# ESP8266-Thing-Dev-4H.net
KiCad netlist of a schematic drawn in EAGLE
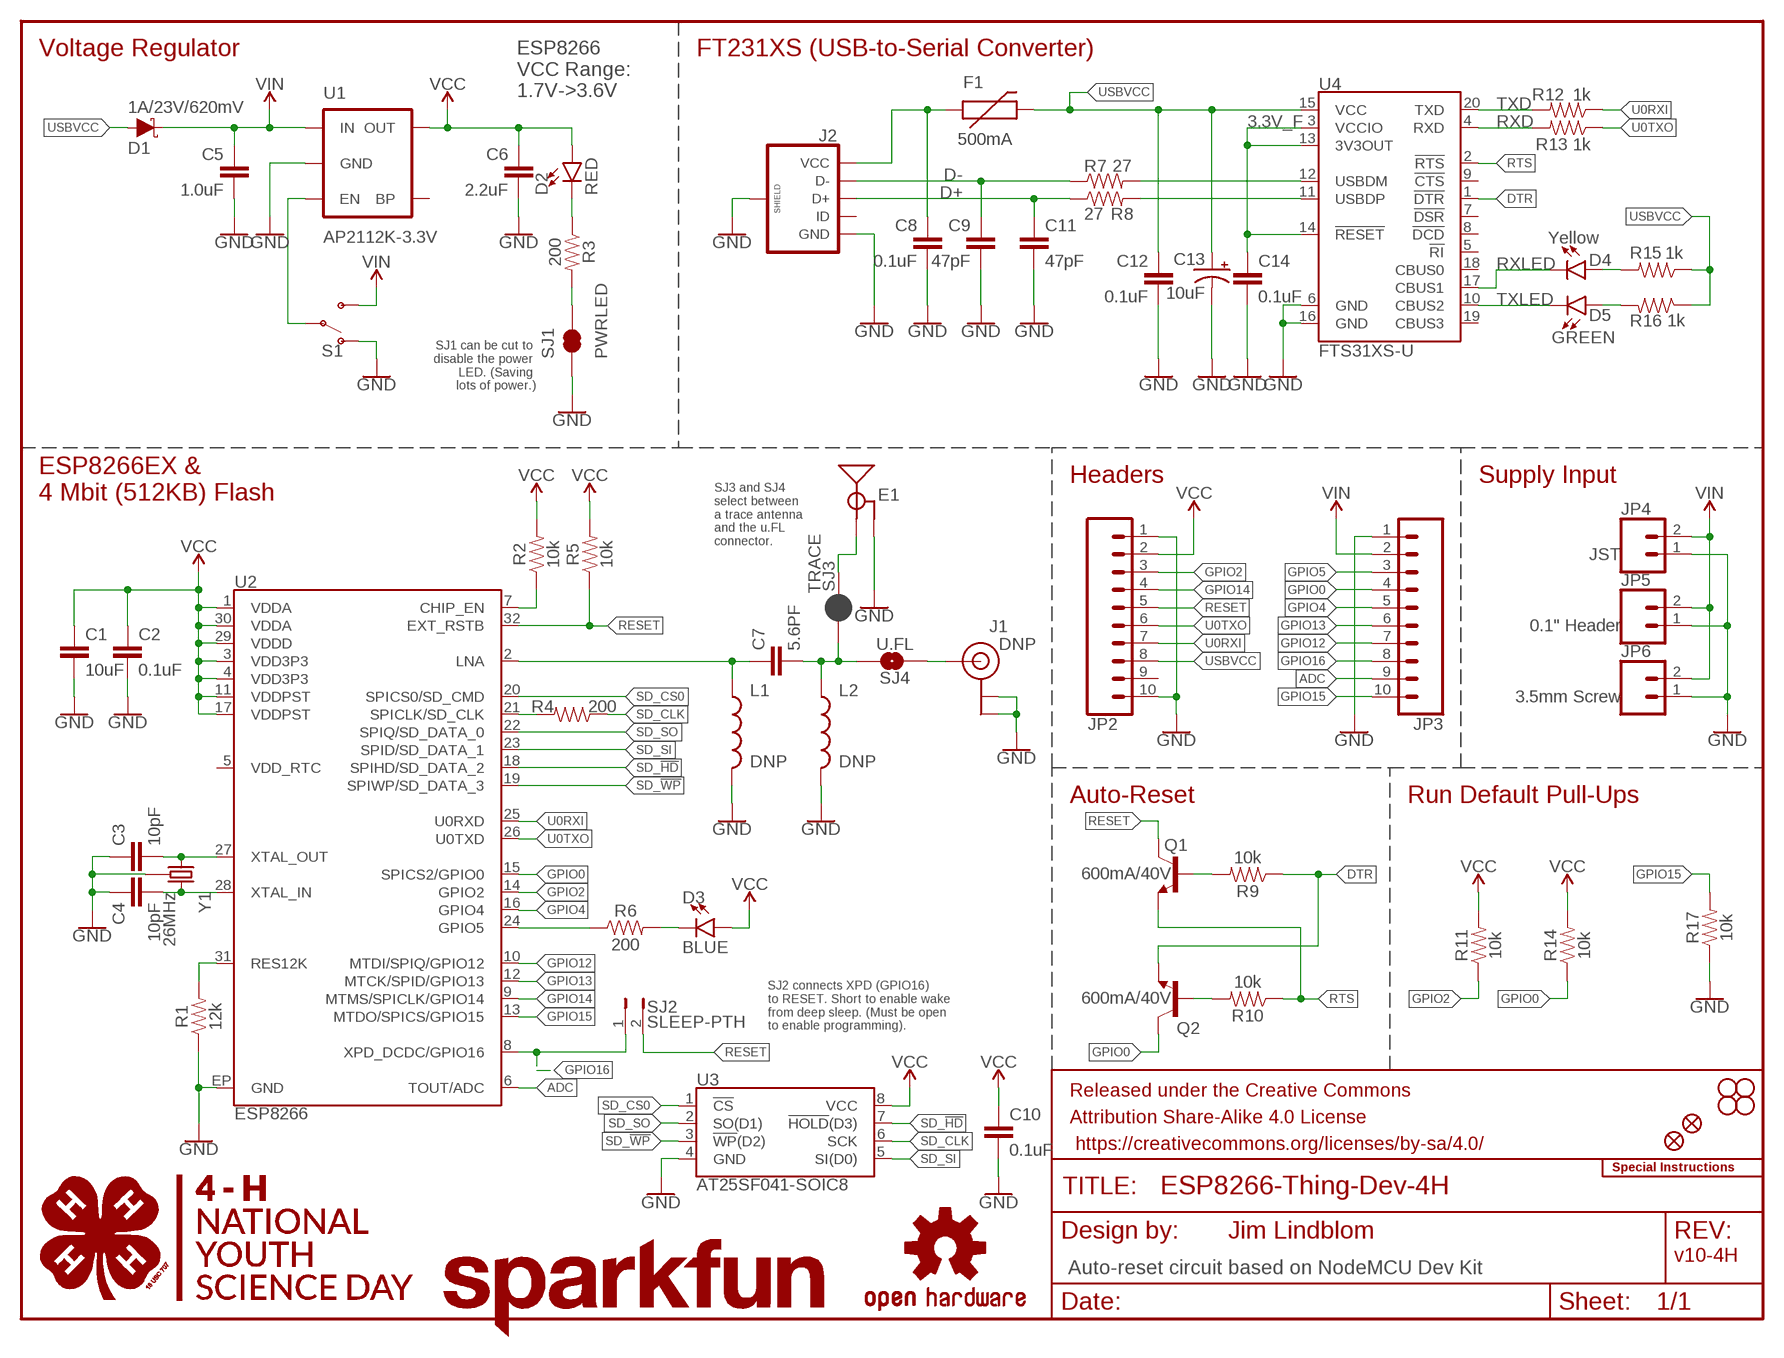
[diagram p0: schematic, sheet 1]

(export (version "E")
  (design (tool "Eeschema 10.0.6"))
  (components
    (comp (ref "C1")
      (value "10uF")
      (footprint "eagle-import:0603")
      (libsource (lib "eagle-import") (part "10UF-0603-6.3V-20%"))
    )
    (comp (ref "C2")
      (value "0.1uF")
      (footprint "eagle-import:0603")
      (libsource (lib "eagle-import") (part "0.1UF-0603-25V-(+80/-20%)"))
    )
    (comp (ref "C3")
      (value "10pF")
      (footprint "eagle-import:0603")
      (libsource (lib "eagle-import") (part "10PF-0603-50V-5%"))
    )
    (comp (ref "C4")
      (value "10pF")
      (footprint "eagle-import:0603")
      (libsource (lib "eagle-import") (part "10PF-0603-50V-5%"))
    )
    (comp (ref "C5")
      (value "1.0uF")
      (footprint "eagle-import:0805")
      (libsource (lib "eagle-import") (part "1.0UF-0805-25V-(+80/-20%)"))
    )
    (comp (ref "C6")
      (value "2.2uF")
      (footprint "eagle-import:0603")
      (libsource (lib "eagle-import") (part "2.2UF-0603-10V-20%"))
    )
    (comp (ref "C7")
      (value "5.6PF")
      (footprint "eagle-import:0603")
      (fields (field (name "PROD_ID") "CAP-12456"))
      (libsource (lib "eagle-import") (part "5.6PF-0603-50V-5%"))
    )
    (comp (ref "C8")
      (value "0.1uF")
      (footprint "eagle-import:0603")
      (libsource (lib "eagle-import") (part "0.1UF-0603-25V-(+80/-20%)"))
    )
    (comp (ref "C9")
      (value "47pF")
      (footprint "eagle-import:0603")
      (libsource (lib "eagle-import") (part "47PF-0603-50V-5%"))
    )
    (comp (ref "C10")
      (value "0.1uF")
      (footprint "eagle-import:0603")
      (libsource (lib "eagle-import") (part "0.1UF-0603-25V-(+80/-20%)"))
    )
    (comp (ref "C11")
      (value "47pF")
      (footprint "eagle-import:0603")
      (libsource (lib "eagle-import") (part "47PF-0603-50V-5%"))
    )
    (comp (ref "C12")
      (value "0.1uF")
      (footprint "eagle-import:0603")
      (libsource (lib "eagle-import") (part "0.1UF-0603-25V-(+80/-20%)"))
    )
    (comp (ref "C13")
      (value "10uF")
      (footprint "eagle-import:EIA3216")
      (libsource (lib "eagle-import") (part "10UF-POLAR-EIA3216-16V-10%(TANT)"))
    )
    (comp (ref "C14")
      (value "0.1uF")
      (footprint "eagle-import:0603")
      (libsource (lib "eagle-import") (part "0.1UF-0603-25V-(+80/-20%)"))
    )
    (comp (ref "D1")
      (value "1A/23V/620mV")
      (footprint "eagle-import:SOD-323")
      (libsource (lib "eagle-import") (part "DIODE-SCHOTTKY-BAT20J"))
    )
    (comp (ref "D2")
      (value "RED")
      (footprint "eagle-import:LED-0603")
      (libsource (lib "eagle-import") (part "LED-RED0603"))
    )
    (comp (ref "D3")
      (value "BLUE")
      (footprint "eagle-import:LED-0603")
      (libsource (lib "eagle-import") (part "LED-BLUE0603"))
    )
    (comp (ref "D4")
      (value "Yellow")
      (footprint "eagle-import:LED-0603")
      (libsource (lib "eagle-import") (part "LED-YELLOW0603"))
    )
    (comp (ref "D5")
      (value "GREEN")
      (footprint "eagle-import:LED-0603")
      (libsource (lib "eagle-import") (part "LED-GREEN0603"))
    )
    (comp (ref "E1")
      (value "ANTENNA-GROUNDEDTRACE-25.7MM")
      (footprint "eagle-import:TRACE_ANTENNA_2.4GHZ_25.7MM")
      (libsource (lib "eagle-import") (part "ANTENNA-GROUNDEDTRACE-25.7MM"))
    )
    (comp (ref "F1")
      (value "500mA")
      (footprint "eagle-import:PTC-1206")
      (libsource (lib "eagle-import") (part "PTCSMD"))
    )
    (comp (ref "FID1")
      (value "FIDUCIAL1X2")
      (footprint "eagle-import:FIDUCIAL-1X2")
      (libsource (lib "eagle-import") (part "FIDUCIAL1X2"))
    )
    (comp (ref "FID2")
      (value "FIDUCIAL1X2")
      (footprint "eagle-import:FIDUCIAL-1X2")
      (libsource (lib "eagle-import") (part "FIDUCIAL1X2"))
    )
    (comp (ref "FRAME1")
      (value "FRAME-LETTER")
      (footprint "eagle-import:CREATIVE_COMMONS")
      (libsource (lib "eagle-import") (part "FRAME-LETTER"))
    )
    (comp (ref "J1")
      (value "U.FL")
      (footprint "eagle-import:U.FL")
      (libsource (lib "eagle-import") (part "U.FL"))
    )
    (comp (ref "J2")
      (value "USB_MICROB_PLUGCONN-11752")
      (footprint "eagle-import:USB-B-MICRO-SMD_V03")
      (libsource (lib "eagle-import") (part "USB_MICROB_PLUGCONN-11752"))
    )
    (comp (ref "JP2")
      (value "CONN_10LOCK_NS")
      (footprint "eagle-import:1X10_LOCK_NS")
      (libsource (lib "eagle-import") (part "CONN_10LOCK_NS"))
    )
    (comp (ref "JP3")
      (value "CONN_10LOCK_NS")
      (footprint "eagle-import:1X10_LOCK_NS")
      (libsource (lib "eagle-import") (part "CONN_10LOCK_NS"))
    )
    (comp (ref "JP4")
      (value "CONN_02JST-PTH-2")
      (footprint "eagle-import:JST-2-PTH")
      (libsource (lib "eagle-import") (part "CONN_02JST-PTH-2"))
    )
    (comp (ref "JP5")
      (value "CONN_021X02_NO_SILK")
      (footprint "eagle-import:1X02_NO_SILK")
      (libsource (lib "eagle-import") (part "CONN_021X02_NO_SILK"))
    )
    (comp (ref "JP6")
      (value "CONN_023.5MM-NO_SILK")
      (footprint "eagle-import:SCREWTERMINAL-3.5MM-2-NS")
      (libsource (lib "eagle-import") (part "CONN_023.5MM-NO_SILK"))
    )
    (comp (ref "L1")
      (value "DNP")
      (footprint "eagle-import:0603")
      (libsource (lib "eagle-import") (part "INDUCTOR0603"))
    )
    (comp (ref "L2")
      (value "DNP")
      (footprint "eagle-import:0603")
      (libsource (lib "eagle-import") (part "INDUCTOR0603"))
    )
    (comp (ref "LOGO1")
      (value "SFE_LOGO_NAME.2_INCH")
      (footprint "eagle-import:SFE_LOGO_NAME_.2")
      (libsource (lib "eagle-import") (part "SFE_LOGO_NAME.2_INCH"))
    )
    (comp (ref "LOGO2")
      (value "OSHW-LOGOS")
      (footprint "eagle-import:OSHW-LOGO-S")
      (libsource (lib "eagle-import") (part "OSHW-LOGOS"))
    )
    (comp (ref "Q1")
      (value "600mA/40V")
      (footprint "eagle-import:SOT23-3")
      (libsource (lib "eagle-import") (part "TRANS_NPN-MMBT2222AL"))
    )
    (comp (ref "Q2")
      (value "600mA/40V")
      (footprint "eagle-import:SOT23-3")
      (libsource (lib "eagle-import") (part "TRANS_NPN-MMBT2222AL"))
    )
    (comp (ref "R1")
      (value "12k")
      (footprint "eagle-import:0603")
      (libsource (lib "eagle-import") (part "12KOHM-0603-1/10W-1%"))
    )
    (comp (ref "R2")
      (value "10k")
      (footprint "eagle-import:0603")
      (libsource (lib "eagle-import") (part "10KOHM-0603-1/10W-1%"))
    )
    (comp (ref "R3")
      (value "200")
      (footprint "eagle-import:0603")
      (libsource (lib "eagle-import") (part "200OHM-0603-1/10W-1%"))
    )
    (comp (ref "R4")
      (value "200")
      (footprint "eagle-import:0603")
      (libsource (lib "eagle-import") (part "200OHM-0603-1/10W-1%"))
    )
    (comp (ref "R5")
      (value "10k")
      (footprint "eagle-import:0603")
      (libsource (lib "eagle-import") (part "10KOHM-0603-1/10W-1%"))
    )
    (comp (ref "R6")
      (value "200")
      (footprint "eagle-import:0603")
      (libsource (lib "eagle-import") (part "200OHM-0603-1/10W-1%"))
    )
    (comp (ref "R7")
      (value "27")
      (footprint "eagle-import:0603")
      (libsource (lib "eagle-import") (part "27OHM-0603-1/10W-1%"))
    )
    (comp (ref "R8")
      (value "27")
      (footprint "eagle-import:0603")
      (libsource (lib "eagle-import") (part "27OHM-0603-1/10W-1%"))
    )
    (comp (ref "R9")
      (value "10k")
      (footprint "eagle-import:0603")
      (libsource (lib "eagle-import") (part "10KOHM-0603-1/10W-1%"))
    )
    (comp (ref "R10")
      (value "10k")
      (footprint "eagle-import:0603")
      (libsource (lib "eagle-import") (part "10KOHM-0603-1/10W-1%"))
    )
    (comp (ref "R11")
      (value "10k")
      (footprint "eagle-import:0603")
      (libsource (lib "eagle-import") (part "10KOHM-0603-1/10W-1%"))
    )
    (comp (ref "R12")
      (value "1k")
      (footprint "eagle-import:0603")
      (libsource (lib "eagle-import") (part "1KOHM-0603-1/10W-1%"))
    )
    (comp (ref "R13")
      (value "1k")
      (footprint "eagle-import:0603")
      (libsource (lib "eagle-import") (part "1KOHM-0603-1/10W-1%"))
    )
    (comp (ref "R14")
      (value "10k")
      (footprint "eagle-import:0603")
      (libsource (lib "eagle-import") (part "10KOHM-0603-1/10W-1%"))
    )
    (comp (ref "R15")
      (value "1k")
      (footprint "eagle-import:0603")
      (libsource (lib "eagle-import") (part "1KOHM-0603-1/10W-1%"))
    )
    (comp (ref "R16")
      (value "1k")
      (footprint "eagle-import:0603")
      (libsource (lib "eagle-import") (part "1KOHM-0603-1/10W-1%"))
    )
    (comp (ref "R17")
      (value "10k")
      (footprint "eagle-import:0603")
      (libsource (lib "eagle-import") (part "10KOHM-0603-1/10W-1%"))
    )
    (comp (ref "S1")
      (value "SWITCH-SPDT-SMD-RIGHT-ANGLE")
      (footprint "eagle-import:SWITCH_SPST_SMD_A")
      (fields (field (name "PROD_ID") "SWCH-10651"))
      (libsource (lib "eagle-import") (part "SWITCH-SPDT-SMD-RIGHT-ANGLE"))
    )
    (comp (ref "SJ1")
      (value "PWRLED")
      (footprint "eagle-import:PAD-JUMPER-2-NC_BY_TRACE_YES_SILK")
      (libsource (lib "eagle-import") (part "JUMPER-PAD-2-NC_BY_TRACE"))
    )
    (comp (ref "SJ2")
      (value "SLEEP-PTH")
      (footprint "eagle-import:PTH-JUMPER-2-NO_NO_SILK")
      (libsource (lib "eagle-import") (part "JUMPER-PTH-2-NO"))
    )
    (comp (ref "SJ3")
      (value "TRACE")
      (footprint "eagle-import:PAD-JUMPER-2-NC_BY_PASTE_NO_SILK")
      (libsource (lib "eagle-import") (part "JUMPER-PAD-2-NC_BY_PASTENO-SILK"))
    )
    (comp (ref "SJ4")
      (value "U.FL")
      (footprint "eagle-import:PAD-JUMPER-2-NO_NO_SILK")
      (libsource (lib "eagle-import") (part "JUMPER-PAD-2-NO"))
    )
    (comp (ref "STANDOFF1")
      (value "STAND-OFF")
      (footprint "eagle-import:STAND-OFF")
      (libsource (lib "eagle-import") (part "STAND-OFF"))
    )
    (comp (ref "STANDOFF2")
      (value "STAND-OFF")
      (footprint "eagle-import:STAND-OFF")
      (libsource (lib "eagle-import") (part "STAND-OFF"))
    )
    (comp (ref "STANDOFF3")
      (value "STAND-OFF")
      (footprint "eagle-import:STAND-OFF")
      (libsource (lib "eagle-import") (part "STAND-OFF"))
    )
    (comp (ref "STANDOFF4")
      (value "STAND-OFF")
      (footprint "eagle-import:STAND-OFF")
      (libsource (lib "eagle-import") (part "STAND-OFF"))
    )
    (comp (ref "U$1")
      (value "4H-NYSD-LOGO-1.35IN")
      (footprint "eagle-import:4H-1.35IN_WIDE")
      (libsource (lib "eagle-import") (part "4H-NYSD-LOGO-1.35IN"))
    )
    (comp (ref "U$2")
      (value "SPECIAL_INSTRUCTIONS-ORDERING")
      (footprint "eagle-import:ORDERING_INSTRUCTIONS")
      (libsource (lib "eagle-import") (part "SPECIAL_INSTRUCTIONS-ORDERING"))
    )
    (comp (ref "U1")
      (value "AP2112K-3.3V")
      (footprint "eagle-import:SOT23-5")
      (libsource (lib "eagle-import") (part "V_REG_LDOSMD"))
    )
    (comp (ref "U2")
      (value "ESP8266")
      (footprint "eagle-import:QFN32-5X5MM")
      (fields (field (name "PROD_ID") "IC-12452"))
      (libsource (lib "eagle-import") (part "ESP8266"))
    )
    (comp (ref "U3")
      (value "AT25SF041-SOIC8")
      (footprint "eagle-import:SO08")
      (libsource (lib "eagle-import") (part "AT25SF041-SOIC8"))
    )
    (comp (ref "U4")
      (value "FTS31XS-U")
      (footprint "eagle-import:SSOP20_L")
      (libsource (lib "eagle-import") (part "FT231XS"))
    )
    (comp (ref "Y1")
      (value "26MHz")
      (footprint "eagle-import:CRYSTAL-SMD-3.2X2.5")
      (libsource (lib "eagle-import") (part "CRYSTAL-GROUNDED3.2X2.5"))
    )
  )
  (nets
    (net (code "1") (name "/3.3V_F") (class "Default")
      (node (ref "C14") (pin "1") (pinfunction "1_1") (pintype "passive"))
      (node (ref "U4") (pin "13") (pinfunction "3V3OUT_13") (pintype "bidirectional"))
      (node (ref "U4") (pin "14") (pinfunction "~{RESET}_14") (pintype "bidirectional"))
      (node (ref "U4") (pin "3") (pinfunction "VCCIO_3") (pintype "bidirectional"))
    )
    (net (code "2") (name "/D+") (class "Default")
      (node (ref "C11") (pin "1") (pinfunction "1_1") (pintype "passive"))
      (node (ref "J2") (pin "D+") (pinfunction "D+_D+") (pintype "bidirectional"))
      (node (ref "R8") (pin "1") (pinfunction "1_1") (pintype "passive"))
    )
    (net (code "3") (name "/D-") (class "Default")
      (node (ref "C9") (pin "1") (pinfunction "1_1") (pintype "passive"))
      (node (ref "J2") (pin "D-") (pinfunction "D-_D-") (pintype "bidirectional"))
      (node (ref "R7") (pin "1") (pinfunction "1_1") (pintype "passive"))
    )
    (net (code "4") (name "/RXD") (class "Default")
      (node (ref "R13") (pin "2") (pinfunction "2_2") (pintype "passive"))
      (node (ref "U4") (pin "4") (pinfunction "RXD_4") (pintype "bidirectional"))
    )
    (net (code "5") (name "/RXLED") (class "Default")
      (node (ref "D4") (pin "C") (pinfunction "C_C") (pintype "passive"))
      (node (ref "U4") (pin "17") (pinfunction "CBUS1_17") (pintype "bidirectional"))
    )
    (net (code "6") (name "/SD_~{HD}") (class "Default")
      (node (ref "U2") (pin "18") (pinfunction "SPIHD/SD_DATA_2_18") (pintype "bidirectional"))
      (node (ref "U3") (pin "7") (pinfunction "~{HOLD}(D3)_7") (pintype "bidirectional"))
    )
    (net (code "7") (name "/SD_~{WP}") (class "Default")
      (node (ref "U2") (pin "19") (pinfunction "SPIWP/SD_DATA_3_19") (pintype "bidirectional"))
      (node (ref "U3") (pin "3") (pinfunction "~{WP}(D2)_3") (pintype "bidirectional"))
    )
    (net (code "8") (name "/TXD") (class "Default")
      (node (ref "R12") (pin "2") (pinfunction "2_2") (pintype "passive"))
      (node (ref "U4") (pin "20") (pinfunction "TXD_20") (pintype "bidirectional"))
    )
    (net (code "9") (name "/TXLED") (class "Default")
      (node (ref "D5") (pin "C") (pinfunction "C_C") (pintype "passive"))
      (node (ref "U4") (pin "10") (pinfunction "CBUS2_10") (pintype "bidirectional"))
    )
    (net (code "10") (name "ADC") (class "Default")
      (node (ref "JP3") (pin "9") (pinfunction "9_9") (pintype "passive"))
      (node (ref "U2") (pin "6") (pinfunction "TOUT/ADC_6") (pintype "bidirectional"))
    )
    (net (code "11") (name "DTR") (class "Default")
      (node (ref "Q2") (pin "2") (pinfunction "E_2") (pintype "passive"))
      (node (ref "R9") (pin "1") (pinfunction "1_1") (pintype "passive"))
      (node (ref "U4") (pin "1") (pinfunction "~{DTR}_1") (pintype "bidirectional"))
    )
    (net (code "12") (name "GND") (class "Default")
      (node (ref "C1") (pin "2") (pinfunction "2_2") (pintype "passive"))
      (node (ref "C10") (pin "2") (pinfunction "2_2") (pintype "passive"))
      (node (ref "C11") (pin "2") (pinfunction "2_2") (pintype "passive"))
      (node (ref "C12") (pin "2") (pinfunction "2_2") (pintype "passive"))
      (node (ref "C13") (pin "-") (pinfunction "-_-") (pintype "passive"))
      (node (ref "C14") (pin "2") (pinfunction "2_2") (pintype "passive"))
      (node (ref "C2") (pin "2") (pinfunction "2_2") (pintype "passive"))
      (node (ref "C3") (pin "1") (pinfunction "1_1") (pintype "passive"))
      (node (ref "C4") (pin "1") (pinfunction "1_1") (pintype "passive"))
      (node (ref "C5") (pin "2") (pinfunction "2_2") (pintype "passive"))
      (node (ref "C6") (pin "2") (pinfunction "2_2") (pintype "passive"))
      (node (ref "C8") (pin "2") (pinfunction "2_2") (pintype "passive"))
      (node (ref "C9") (pin "2") (pinfunction "2_2") (pintype "passive"))
      (node (ref "E1") (pin "GND") (pinfunction "GND_GND") (pintype "bidirectional"))
      (node (ref "E1") (pin "GND2") (pinfunction "GND_GND2") (pintype "bidirectional"))
      (node (ref "J1") (pin "P$1") (pinfunction "GND_P$1") (pintype "bidirectional"))
      (node (ref "J1") (pin "P$2") (pinfunction "GND_P$2") (pintype "bidirectional"))
      (node (ref "J2") (pin "GND") (pinfunction "GND_GND") (pintype "bidirectional"))
      (node (ref "J2") (pin "SHIELD1") (pinfunction "SHIELD_SHIELD1") (pintype "bidirectional"))
      (node (ref "J2") (pin "SHIELD2") (pinfunction "SHIELD_SHIELD2") (pintype "bidirectional"))
      (node (ref "J2") (pin "SHIELD3") (pinfunction "SHIELD_SHIELD3") (pintype "bidirectional"))
      (node (ref "JP2") (pin "1") (pinfunction "1_1") (pintype "passive"))
      (node (ref "JP2") (pin "10") (pinfunction "10_10") (pintype "passive"))
      (node (ref "JP3") (pin "1") (pinfunction "1_1") (pintype "passive"))
      (node (ref "JP4") (pin "1") (pinfunction "1_1") (pintype "passive"))
      (node (ref "JP5") (pin "1") (pinfunction "1_1") (pintype "passive"))
      (node (ref "JP6") (pin "1") (pinfunction "1_1") (pintype "passive"))
      (node (ref "L1") (pin "2") (pinfunction "2_2") (pintype "passive"))
      (node (ref "L2") (pin "2") (pinfunction "2_2") (pintype "passive"))
      (node (ref "R1") (pin "1") (pinfunction "1_1") (pintype "passive"))
      (node (ref "R17") (pin "1") (pinfunction "1_1") (pintype "passive"))
      (node (ref "S1") (pin "1") (pinfunction "O_1") (pintype "passive"))
      (node (ref "SJ1") (pin "1") (pinfunction "1_1") (pintype "passive"))
      (node (ref "U1") (pin "2") (pinfunction "GND_2") (pintype "input"))
      (node (ref "U2") (pin "EP") (pinfunction "GND_EP") (pintype "bidirectional"))
      (node (ref "U3") (pin "4") (pinfunction "GND_4") (pintype "bidirectional"))
      (node (ref "U4") (pin "16") (pinfunction "GND_16") (pintype "bidirectional"))
      (node (ref "U4") (pin "6") (pinfunction "GND_6") (pintype "bidirectional"))
      (node (ref "Y1") (pin "2") (pinfunction "GND_2") (pintype "passive"))
      (node (ref "Y1") (pin "4") (pinfunction "GND_4") (pintype "passive"))
    )
    (net (code "13") (name "GPIO0") (class "Default")
      (node (ref "JP3") (pin "4") (pinfunction "4_4") (pintype "passive"))
      (node (ref "Q2") (pin "3") (pinfunction "C_3") (pintype "passive"))
      (node (ref "R14") (pin "1") (pinfunction "1_1") (pintype "passive"))
      (node (ref "U2") (pin "15") (pinfunction "SPICS2/GPIO0_15") (pintype "bidirectional"))
    )
    (net (code "14") (name "GPIO2") (class "Default")
      (node (ref "JP2") (pin "3") (pinfunction "3_3") (pintype "passive"))
      (node (ref "R11") (pin "1") (pinfunction "1_1") (pintype "passive"))
      (node (ref "U2") (pin "14") (pinfunction "GPIO2_14") (pintype "bidirectional"))
    )
    (net (code "15") (name "GPIO4") (class "Default")
      (node (ref "JP3") (pin "5") (pinfunction "5_5") (pintype "passive"))
      (node (ref "U2") (pin "16") (pinfunction "GPIO4_16") (pintype "bidirectional"))
    )
    (net (code "16") (name "GPIO5") (class "Default")
      (node (ref "JP3") (pin "3") (pinfunction "3_3") (pintype "passive"))
      (node (ref "R6") (pin "1") (pinfunction "1_1") (pintype "passive"))
      (node (ref "U2") (pin "24") (pinfunction "GPIO5_24") (pintype "bidirectional"))
    )
    (net (code "17") (name "GPIO12") (class "Default")
      (node (ref "JP3") (pin "7") (pinfunction "7_7") (pintype "passive"))
      (node (ref "U2") (pin "10") (pinfunction "MTDI/SPIQ/GPIO12_10") (pintype "bidirectional"))
    )
    (net (code "18") (name "GPIO13") (class "Default")
      (node (ref "JP3") (pin "6") (pinfunction "6_6") (pintype "passive"))
      (node (ref "U2") (pin "12") (pinfunction "MTCK/SPID/GPIO13_12") (pintype "bidirectional"))
    )
    (net (code "19") (name "GPIO14") (class "Default")
      (node (ref "JP2") (pin "4") (pinfunction "4_4") (pintype "passive"))
      (node (ref "U2") (pin "9") (pinfunction "MTMS/SPICLK/GPIO14_9") (pintype "bidirectional"))
    )
    (net (code "20") (name "GPIO15") (class "Default")
      (node (ref "JP3") (pin "10") (pinfunction "10_10") (pintype "passive"))
      (node (ref "R17") (pin "2") (pinfunction "2_2") (pintype "passive"))
      (node (ref "U2") (pin "13") (pinfunction "MTDO/SPICS/GPIO15_13") (pintype "bidirectional"))
    )
    (net (code "21") (name "GPIO16") (class "Default")
      (node (ref "JP3") (pin "8") (pinfunction "8_8") (pintype "passive"))
      (node (ref "SJ2") (pin "1") (pinfunction "1_1") (pintype "passive"))
      (node (ref "U2") (pin "8") (pinfunction "XPD_DCDC/GPIO16_8") (pintype "bidirectional"))
    )
    (net (code "22") (name "Net-(C7-Pad2)") (class "Default")
      (node (ref "C7") (pin "2") (pinfunction "2_2") (pintype "passive"))
      (node (ref "L2") (pin "1") (pinfunction "1_1") (pintype "passive"))
      (node (ref "SJ3") (pin "1") (pinfunction "1_1") (pintype "passive"))
      (node (ref "SJ4") (pin "2") (pinfunction "2_2") (pintype "passive"))
    )
    (net (code "23") (name "Net-(D2-PadC)") (class "Default")
      (node (ref "D2") (pin "C") (pinfunction "C_C") (pintype "passive"))
      (node (ref "R3") (pin "1") (pinfunction "1_1") (pintype "passive"))
    )
    (net (code "24") (name "Net-(D3-PadC)") (class "Default")
      (node (ref "D3") (pin "C") (pinfunction "C_C") (pintype "passive"))
      (node (ref "R6") (pin "2") (pinfunction "2_2") (pintype "passive"))
    )
    (net (code "25") (name "Net-(D4-PadA)") (class "Default")
      (node (ref "D4") (pin "A") (pinfunction "A_A") (pintype "passive"))
      (node (ref "R15") (pin "2") (pinfunction "2_2") (pintype "passive"))
    )
    (net (code "26") (name "Net-(D5-PadA)") (class "Default")
      (node (ref "D5") (pin "A") (pinfunction "A_A") (pintype "passive"))
      (node (ref "R16") (pin "2") (pinfunction "2_2") (pintype "passive"))
    )
    (net (code "27") (name "Net-(E1-SIGNAL)") (class "Default")
      (node (ref "E1") (pin "ANT") (pinfunction "SIGNAL_ANT") (pintype "bidirectional"))
      (node (ref "SJ3") (pin "2") (pinfunction "2_2") (pintype "passive"))
    )
    (net (code "28") (name "Net-(J1-SIGNAL)") (class "Default")
      (node (ref "J1") (pin "P$3") (pinfunction "SIGNAL_P$3") (pintype "bidirectional"))
      (node (ref "SJ4") (pin "1") (pinfunction "1_1") (pintype "passive"))
    )
    (net (code "29") (name "Net-(J2-VCC)") (class "Default")
      (node (ref "C8") (pin "1") (pinfunction "1_1") (pintype "passive"))
      (node (ref "F1") (pin "1") (pinfunction "1_1") (pintype "bidirectional"))
      (node (ref "J2") (pin "VBUS") (pinfunction "VCC_VBUS") (pintype "bidirectional"))
    )
    (net (code "30") (name "Net-(Q1-B)") (class "Default")
      (node (ref "Q1") (pin "1") (pinfunction "B_1") (pintype "passive"))
      (node (ref "R9") (pin "2") (pinfunction "2_2") (pintype "passive"))
    )
    (net (code "31") (name "Net-(Q2-B)") (class "Default")
      (node (ref "Q2") (pin "1") (pinfunction "B_1") (pintype "passive"))
      (node (ref "R10") (pin "2") (pinfunction "2_2") (pintype "passive"))
    )
    (net (code "32") (name "Net-(R3-Pad2)") (class "Default")
      (node (ref "R3") (pin "2") (pinfunction "2_2") (pintype "passive"))
      (node (ref "SJ1") (pin "2") (pinfunction "2_2") (pintype "passive"))
    )
    (net (code "33") (name "Net-(S1-P)") (class "Default")
      (node (ref "S1") (pin "2") (pinfunction "P_2") (pintype "passive"))
      (node (ref "U1") (pin "3") (pinfunction "EN_3") (pintype "input"))
    )
    (net (code "34") (name "Net-(U2-CHIP_EN)") (class "Default")
      (node (ref "R2") (pin "1") (pinfunction "1_1") (pintype "passive"))
      (node (ref "U2") (pin "7") (pinfunction "CHIP_EN_7") (pintype "bidirectional"))
    )
    (net (code "35") (name "Net-(U2-LNA)") (class "Default")
      (node (ref "C7") (pin "1") (pinfunction "1_1") (pintype "passive"))
      (node (ref "L1") (pin "1") (pinfunction "1_1") (pintype "passive"))
      (node (ref "U2") (pin "2") (pinfunction "LNA_2") (pintype "bidirectional"))
    )
    (net (code "36") (name "Net-(U2-RES12K)") (class "Default")
      (node (ref "R1") (pin "2") (pinfunction "2_2") (pintype "passive"))
      (node (ref "U2") (pin "31") (pinfunction "RES12K_31") (pintype "bidirectional"))
    )
    (net (code "37") (name "Net-(U2-SPICLK{slash}SD_CLK)") (class "Default")
      (node (ref "R4") (pin "2") (pinfunction "2_2") (pintype "passive"))
      (node (ref "U2") (pin "21") (pinfunction "SPICLK/SD_CLK_21") (pintype "bidirectional"))
    )
    (net (code "38") (name "Net-(U2-XTAL_IN)") (class "Default")
      (node (ref "C4") (pin "2") (pinfunction "2_2") (pintype "passive"))
      (node (ref "U2") (pin "28") (pinfunction "XTAL_IN_28") (pintype "bidirectional"))
      (node (ref "Y1") (pin "3") (pinfunction "2_3") (pintype "passive"))
    )
    (net (code "39") (name "Net-(U2-XTAL_OUT)") (class "Default")
      (node (ref "C3") (pin "2") (pinfunction "2_2") (pintype "passive"))
      (node (ref "U2") (pin "27") (pinfunction "XTAL_OUT_27") (pintype "bidirectional"))
      (node (ref "Y1") (pin "1") (pinfunction "1_1") (pintype "passive"))
    )
    (net (code "40") (name "Net-(U4-USBDM)") (class "Default")
      (node (ref "R7") (pin "2") (pinfunction "2_2") (pintype "passive"))
      (node (ref "U4") (pin "12") (pinfunction "USBDM_12") (pintype "bidirectional"))
    )
    (net (code "41") (name "Net-(U4-USBDP)") (class "Default")
      (node (ref "R8") (pin "2") (pinfunction "2_2") (pintype "passive"))
      (node (ref "U4") (pin "11") (pinfunction "USBDP_11") (pintype "bidirectional"))
    )
    (net (code "42") (name "RESET") (class "Default")
      (node (ref "JP2") (pin "5") (pinfunction "5_5") (pintype "passive"))
      (node (ref "Q1") (pin "3") (pinfunction "C_3") (pintype "passive"))
      (node (ref "R5") (pin "1") (pinfunction "1_1") (pintype "passive"))
      (node (ref "SJ2") (pin "2") (pinfunction "2_2") (pintype "passive"))
      (node (ref "U2") (pin "32") (pinfunction "EXT_RSTB_32") (pintype "bidirectional"))
    )
    (net (code "43") (name "RTS") (class "Default")
      (node (ref "Q1") (pin "2") (pinfunction "E_2") (pintype "passive"))
      (node (ref "R10") (pin "1") (pinfunction "1_1") (pintype "passive"))
      (node (ref "U4") (pin "2") (pinfunction "~{RTS}_2") (pintype "bidirectional"))
    )
    (net (code "44") (name "SD_CLK") (class "Default")
      (node (ref "R4") (pin "1") (pinfunction "1_1") (pintype "passive"))
      (node (ref "U3") (pin "6") (pinfunction "SCK_6") (pintype "bidirectional"))
    )
    (net (code "45") (name "SD_CS0") (class "Default")
      (node (ref "U2") (pin "20") (pinfunction "SPICS0/SD_CMD_20") (pintype "bidirectional"))
      (node (ref "U3") (pin "1") (pinfunction "~{CS}_1") (pintype "bidirectional"))
    )
    (net (code "46") (name "SD_SI") (class "Default")
      (node (ref "U2") (pin "23") (pinfunction "SPID/SD_DATA_1_23") (pintype "bidirectional"))
      (node (ref "U3") (pin "5") (pinfunction "SI(D0)_5") (pintype "bidirectional"))
    )
    (net (code "47") (name "SD_SO") (class "Default")
      (node (ref "U2") (pin "22") (pinfunction "SPIQ/SD_DATA_0_22") (pintype "bidirectional"))
      (node (ref "U3") (pin "2") (pinfunction "SO(D1)_2") (pintype "bidirectional"))
    )
    (net (code "48") (name "U0RXI") (class "Default")
      (node (ref "JP2") (pin "7") (pinfunction "7_7") (pintype "passive"))
      (node (ref "R12") (pin "1") (pinfunction "1_1") (pintype "passive"))
      (node (ref "U2") (pin "25") (pinfunction "U0RXD_25") (pintype "bidirectional"))
    )
    (net (code "49") (name "U0TXO") (class "Default")
      (node (ref "JP2") (pin "6") (pinfunction "6_6") (pintype "passive"))
      (node (ref "R13") (pin "1") (pinfunction "1_1") (pintype "passive"))
      (node (ref "U2") (pin "26") (pinfunction "U0TXD_26") (pintype "bidirectional"))
    )
    (net (code "50") (name "USBVCC") (class "Default")
      (node (ref "C12") (pin "1") (pinfunction "1_1") (pintype "passive"))
      (node (ref "C13") (pin "+") (pinfunction "+_+") (pintype "passive"))
      (node (ref "D1") (pin "A") (pinfunction "A_A") (pintype "passive"))
      (node (ref "F1") (pin "2") (pinfunction "2_2") (pintype "bidirectional"))
      (node (ref "JP2") (pin "8") (pinfunction "8_8") (pintype "passive"))
      (node (ref "R15") (pin "1") (pinfunction "1_1") (pintype "passive"))
      (node (ref "R16") (pin "1") (pinfunction "1_1") (pintype "passive"))
      (node (ref "U4") (pin "15") (pinfunction "VCC_15") (pintype "bidirectional"))
    )
    (net (code "51") (name "VCC") (class "Default")
      (node (ref "C1") (pin "1") (pinfunction "1_1") (pintype "passive"))
      (node (ref "C10") (pin "1") (pinfunction "1_1") (pintype "passive"))
      (node (ref "C2") (pin "1") (pinfunction "1_1") (pintype "passive"))
      (node (ref "C6") (pin "1") (pinfunction "1_1") (pintype "passive"))
      (node (ref "D2") (pin "A") (pinfunction "A_A") (pintype "passive"))
      (node (ref "D3") (pin "A") (pinfunction "A_A") (pintype "passive"))
      (node (ref "JP2") (pin "2") (pinfunction "2_2") (pintype "passive"))
      (node (ref "R11") (pin "2") (pinfunction "2_2") (pintype "passive"))
      (node (ref "R14") (pin "2") (pinfunction "2_2") (pintype "passive"))
      (node (ref "R2") (pin "2") (pinfunction "2_2") (pintype "passive"))
      (node (ref "R5") (pin "2") (pinfunction "2_2") (pintype "passive"))
      (node (ref "U1") (pin "5") (pinfunction "OUT_5") (pintype "passive"))
      (node (ref "U2") (pin "1") (pinfunction "VDDA_1") (pintype "bidirectional"))
      (node (ref "U2") (pin "11") (pinfunction "VDDPST_11") (pintype "bidirectional"))
      (node (ref "U2") (pin "17") (pinfunction "VDDPST_17") (pintype "bidirectional"))
      (node (ref "U2") (pin "29") (pinfunction "VDDD_29") (pintype "bidirectional"))
      (node (ref "U2") (pin "3") (pinfunction "VDD3P3_3") (pintype "bidirectional"))
      (node (ref "U2") (pin "30") (pinfunction "VDDA_30") (pintype "bidirectional"))
      (node (ref "U2") (pin "4") (pinfunction "VDD3P3_4") (pintype "bidirectional"))
      (node (ref "U3") (pin "8") (pinfunction "VCC_8") (pintype "bidirectional"))
    )
    (net (code "52") (name "VIN") (class "Default")
      (node (ref "C5") (pin "1") (pinfunction "1_1") (pintype "passive"))
      (node (ref "D1") (pin "C") (pinfunction "C_C") (pintype "passive"))
      (node (ref "JP3") (pin "2") (pinfunction "2_2") (pintype "passive"))
      (node (ref "JP4") (pin "2") (pinfunction "2_2") (pintype "passive"))
      (node (ref "JP5") (pin "2") (pinfunction "2_2") (pintype "passive"))
      (node (ref "JP6") (pin "2") (pinfunction "2_2") (pintype "passive"))
      (node (ref "S1") (pin "3") (pinfunction "S_3") (pintype "passive"))
      (node (ref "U1") (pin "1") (pinfunction "IN_1") (pintype "input"))
    )
    (net (code "53") (name "unconnected-(J2-PadID)") (class "Default")
      (node (ref "J2") (pin "ID") (pinfunction "ID_ID") (pintype "bidirectional"))
    )
    (net (code "54") (name "unconnected-(JP2-Pad9)") (class "Default")
      (node (ref "JP2") (pin "9") (pinfunction "9_9") (pintype "passive"))
    )
    (net (code "55") (name "unconnected-(U1-BP-Pad4)") (class "Default")
      (node (ref "U1") (pin "4") (pinfunction "BP_4") (pintype "input"))
    )
    (net (code "56") (name "unconnected-(U2-VDD_RTC-Pad5)") (class "Default")
      (node (ref "U2") (pin "5") (pinfunction "VDD_RTC_5") (pintype "bidirectional"))
    )
    (net (code "57") (name "unconnected-(U4-CBUS0-Pad18)") (class "Default")
      (node (ref "U4") (pin "18") (pinfunction "CBUS0_18") (pintype "bidirectional"))
    )
    (net (code "58") (name "unconnected-(U4-CBUS3-Pad19)") (class "Default")
      (node (ref "U4") (pin "19") (pinfunction "CBUS3_19") (pintype "bidirectional"))
    )
    (net (code "59") (name "unconnected-(U4-~{CTS}-Pad9)") (class "Default")
      (node (ref "U4") (pin "9") (pinfunction "~{CTS}_9") (pintype "bidirectional"))
    )
    (net (code "60") (name "unconnected-(U4-~{DCD}-Pad8)") (class "Default")
      (node (ref "U4") (pin "8") (pinfunction "~{DCD}_8") (pintype "bidirectional"))
    )
    (net (code "61") (name "unconnected-(U4-~{DSR}-Pad7)") (class "Default")
      (node (ref "U4") (pin "7") (pinfunction "~{DSR}_7") (pintype "bidirectional"))
    )
    (net (code "62") (name "unconnected-(U4-~{RI}-Pad5)") (class "Default")
      (node (ref "U4") (pin "5") (pinfunction "~{RI}_5") (pintype "bidirectional"))
    )
  )
)
